# TKeyboard2_2021-07-30.net
KiCad netlist of a schematic drawn in Altium Designer
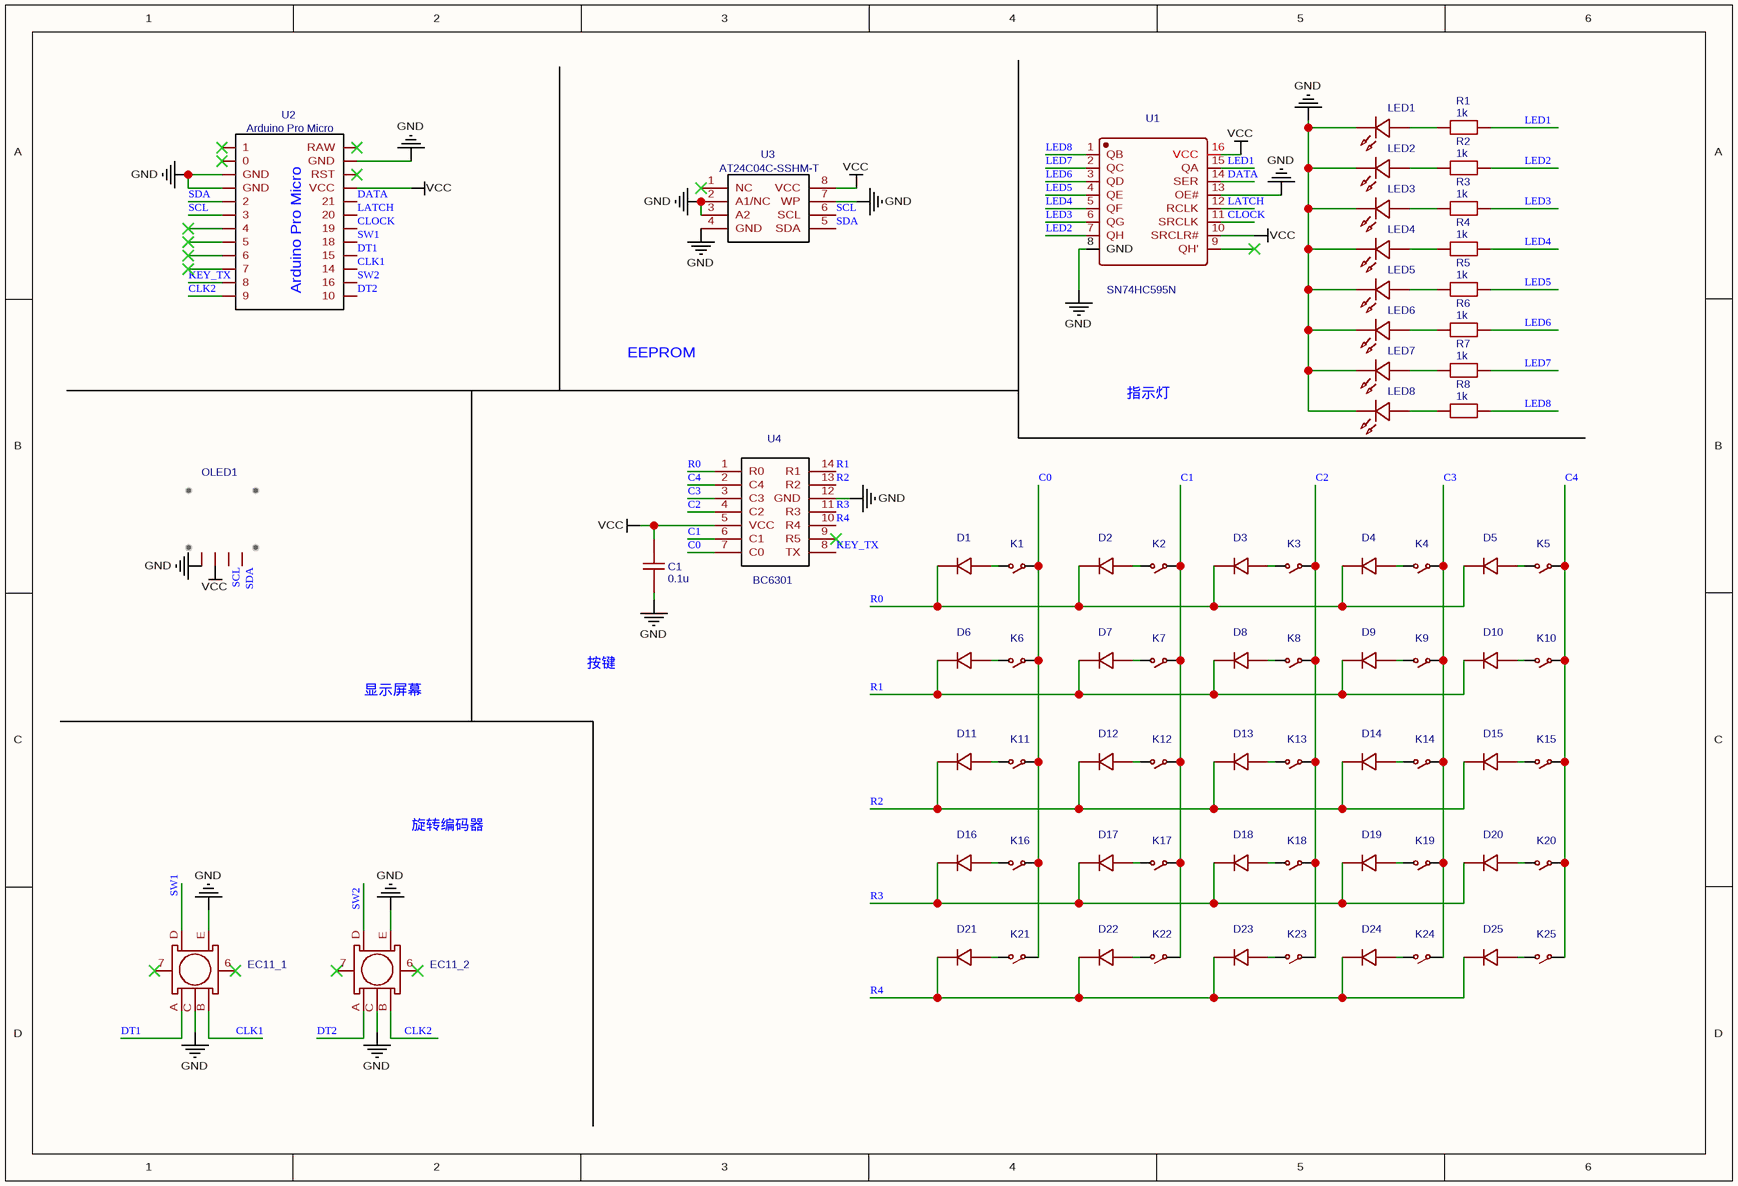
[diagram p0: TKeyboard2_2021-07-30.schdoc]

(export (version "E")
  (design (tool "Eeschema 10.0.6"))
  (components
    (comp (ref "C1")
      (value "0.1u")
      (fields (field (name "CONTRIBUTOR") "LCEDA_Lib"))
      (libsource (lib "altium-import") (part "root_1_0.1u_"))
    )
    (comp (ref "D1")
      (value "1N4148WS")
      (fields (field (name "BOM_SUPPLIER PART") "C179718") (field (name "CONTRIBUTOR") "LCSC"))
      (libsource (lib "altium-import") (part "root_0_1N4148WS_"))
    )
    (comp (ref "D2")
      (value "1N4148WS")
      (fields (field (name "BOM_SUPPLIER PART") "C179718") (field (name "CONTRIBUTOR") "LCSC"))
      (libsource (lib "altium-import") (part "root_0_1N4148WS_"))
    )
    (comp (ref "D3")
      (value "1N4148WS")
      (fields (field (name "BOM_SUPPLIER PART") "C179718") (field (name "CONTRIBUTOR") "LCSC"))
      (libsource (lib "altium-import") (part "root_0_1N4148WS_"))
    )
    (comp (ref "D4")
      (value "1N4148WS")
      (fields (field (name "BOM_SUPPLIER PART") "C179718") (field (name "CONTRIBUTOR") "LCSC"))
      (libsource (lib "altium-import") (part "root_0_1N4148WS_"))
    )
    (comp (ref "D5")
      (value "1N4148WS")
      (fields (field (name "BOM_SUPPLIER PART") "C179718") (field (name "CONTRIBUTOR") "LCSC"))
      (libsource (lib "altium-import") (part "root_0_1N4148WS_"))
    )
    (comp (ref "D6")
      (value "1N4148WS")
      (fields (field (name "BOM_SUPPLIER PART") "C179718") (field (name "CONTRIBUTOR") "LCSC"))
      (libsource (lib "altium-import") (part "root_0_1N4148WS_"))
    )
    (comp (ref "D7")
      (value "1N4148WS")
      (fields (field (name "BOM_SUPPLIER PART") "C179718") (field (name "CONTRIBUTOR") "LCSC"))
      (libsource (lib "altium-import") (part "root_0_1N4148WS_"))
    )
    (comp (ref "D8")
      (value "1N4148WS")
      (fields (field (name "BOM_SUPPLIER PART") "C179718") (field (name "CONTRIBUTOR") "LCSC"))
      (libsource (lib "altium-import") (part "root_0_1N4148WS_"))
    )
    (comp (ref "D9")
      (value "1N4148WS")
      (fields (field (name "BOM_SUPPLIER PART") "C179718") (field (name "CONTRIBUTOR") "LCSC"))
      (libsource (lib "altium-import") (part "root_0_1N4148WS_"))
    )
    (comp (ref "D10")
      (value "1N4148WS")
      (fields (field (name "BOM_SUPPLIER PART") "C179718") (field (name "CONTRIBUTOR") "LCSC"))
      (libsource (lib "altium-import") (part "root_0_1N4148WS_"))
    )
    (comp (ref "D11")
      (value "1N4148WS")
      (fields (field (name "BOM_SUPPLIER PART") "C179718") (field (name "CONTRIBUTOR") "LCSC"))
      (libsource (lib "altium-import") (part "root_0_1N4148WS_"))
    )
    (comp (ref "D12")
      (value "1N4148WS")
      (fields (field (name "BOM_SUPPLIER PART") "C179718") (field (name "CONTRIBUTOR") "LCSC"))
      (libsource (lib "altium-import") (part "root_0_1N4148WS_"))
    )
    (comp (ref "D13")
      (value "1N4148WS")
      (fields (field (name "BOM_SUPPLIER PART") "C179718") (field (name "CONTRIBUTOR") "LCSC"))
      (libsource (lib "altium-import") (part "root_0_1N4148WS_"))
    )
    (comp (ref "D14")
      (value "1N4148WS")
      (fields (field (name "BOM_SUPPLIER PART") "C179718") (field (name "CONTRIBUTOR") "LCSC"))
      (libsource (lib "altium-import") (part "root_0_1N4148WS_"))
    )
    (comp (ref "D15")
      (value "1N4148WS")
      (fields (field (name "BOM_SUPPLIER PART") "C179718") (field (name "CONTRIBUTOR") "LCSC"))
      (libsource (lib "altium-import") (part "root_0_1N4148WS_"))
    )
    (comp (ref "D16")
      (value "1N4148WS")
      (fields (field (name "BOM_SUPPLIER PART") "C179718") (field (name "CONTRIBUTOR") "LCSC"))
      (libsource (lib "altium-import") (part "root_0_1N4148WS_"))
    )
    (comp (ref "D17")
      (value "1N4148WS")
      (fields (field (name "BOM_SUPPLIER PART") "C179718") (field (name "CONTRIBUTOR") "LCSC"))
      (libsource (lib "altium-import") (part "root_0_1N4148WS_"))
    )
    (comp (ref "D18")
      (value "1N4148WS")
      (fields (field (name "BOM_SUPPLIER PART") "C179718") (field (name "CONTRIBUTOR") "LCSC"))
      (libsource (lib "altium-import") (part "root_0_1N4148WS_"))
    )
    (comp (ref "D19")
      (value "1N4148WS")
      (fields (field (name "BOM_SUPPLIER PART") "C179718") (field (name "CONTRIBUTOR") "LCSC"))
      (libsource (lib "altium-import") (part "root_0_1N4148WS_"))
    )
    (comp (ref "D20")
      (value "1N4148WS")
      (fields (field (name "BOM_SUPPLIER PART") "C179718") (field (name "CONTRIBUTOR") "LCSC"))
      (libsource (lib "altium-import") (part "root_0_1N4148WS_"))
    )
    (comp (ref "D21")
      (value "1N4148WS")
      (fields (field (name "BOM_SUPPLIER PART") "C179718") (field (name "CONTRIBUTOR") "LCSC"))
      (libsource (lib "altium-import") (part "root_0_1N4148WS_"))
    )
    (comp (ref "D22")
      (value "1N4148WS")
      (fields (field (name "BOM_SUPPLIER PART") "C179718") (field (name "CONTRIBUTOR") "LCSC"))
      (libsource (lib "altium-import") (part "root_0_1N4148WS_"))
    )
    (comp (ref "D23")
      (value "1N4148WS")
      (fields (field (name "BOM_SUPPLIER PART") "C179718") (field (name "CONTRIBUTOR") "LCSC"))
      (libsource (lib "altium-import") (part "root_0_1N4148WS_"))
    )
    (comp (ref "D24")
      (value "1N4148WS")
      (fields (field (name "BOM_SUPPLIER PART") "C179718") (field (name "CONTRIBUTOR") "LCSC"))
      (libsource (lib "altium-import") (part "root_0_1N4148WS_"))
    )
    (comp (ref "D25")
      (value "1N4148WS")
      (fields (field (name "BOM_SUPPLIER PART") "C179718") (field (name "CONTRIBUTOR") "LCSC"))
      (libsource (lib "altium-import") (part "root_0_1N4148WS_"))
    )
    (comp (ref "EC11_1")
      (value "EC11E152T409")
      (fields (field (name "BOM_SUPPLIER PART") "C110314") (field (name "CONTRIBUTOR") "LCSC"))
      (libsource (lib "altium-import") (part "root_0_EC11E152T409_"))
    )
    (comp (ref "EC11_2")
      (value "EC11E152T409")
      (fields (field (name "BOM_SUPPLIER PART") "C110314") (field (name "CONTRIBUTOR") "LCSC"))
      (libsource (lib "altium-import") (part "root_0_EC11E152T409_"))
    )
    (comp (ref "K1")
      (value "CHERRY")
      (fields (field (name "CONTRIBUTOR") "nicholasyoo"))
      (libsource (lib "altium-import") (part "root_0_CHERRY_"))
    )
    (comp (ref "K2")
      (value "CHERRY")
      (fields (field (name "CONTRIBUTOR") "nicholasyoo"))
      (libsource (lib "altium-import") (part "root_0_CHERRY_"))
    )
    (comp (ref "K3")
      (value "CHERRY")
      (fields (field (name "CONTRIBUTOR") "nicholasyoo"))
      (libsource (lib "altium-import") (part "root_0_CHERRY_"))
    )
    (comp (ref "K4")
      (value "CHERRY")
      (fields (field (name "CONTRIBUTOR") "nicholasyoo"))
      (libsource (lib "altium-import") (part "root_0_CHERRY_"))
    )
    (comp (ref "K5")
      (value "CHERRY")
      (fields (field (name "CONTRIBUTOR") "nicholasyoo"))
      (libsource (lib "altium-import") (part "root_0_CHERRY_"))
    )
    (comp (ref "K6")
      (value "CHERRY")
      (fields (field (name "CONTRIBUTOR") "nicholasyoo"))
      (libsource (lib "altium-import") (part "root_0_CHERRY_"))
    )
    (comp (ref "K7")
      (value "CHERRY")
      (fields (field (name "CONTRIBUTOR") "nicholasyoo"))
      (libsource (lib "altium-import") (part "root_0_CHERRY_"))
    )
    (comp (ref "K8")
      (value "CHERRY")
      (fields (field (name "CONTRIBUTOR") "nicholasyoo"))
      (libsource (lib "altium-import") (part "root_0_CHERRY_"))
    )
    (comp (ref "K9")
      (value "CHERRY")
      (fields (field (name "CONTRIBUTOR") "nicholasyoo"))
      (libsource (lib "altium-import") (part "root_0_CHERRY_"))
    )
    (comp (ref "K10")
      (value "CHERRY")
      (fields (field (name "CONTRIBUTOR") "nicholasyoo"))
      (libsource (lib "altium-import") (part "root_0_CHERRY_"))
    )
    (comp (ref "K11")
      (value "CHERRY")
      (fields (field (name "CONTRIBUTOR") "nicholasyoo"))
      (libsource (lib "altium-import") (part "root_0_CHERRY_"))
    )
    (comp (ref "K12")
      (value "CHERRY")
      (fields (field (name "CONTRIBUTOR") "nicholasyoo"))
      (libsource (lib "altium-import") (part "root_0_CHERRY_"))
    )
    (comp (ref "K13")
      (value "CHERRY")
      (fields (field (name "CONTRIBUTOR") "nicholasyoo"))
      (libsource (lib "altium-import") (part "root_0_CHERRY_"))
    )
    (comp (ref "K14")
      (value "CHERRY")
      (fields (field (name "CONTRIBUTOR") "nicholasyoo"))
      (libsource (lib "altium-import") (part "root_0_CHERRY_"))
    )
    (comp (ref "K15")
      (value "CHERRY")
      (fields (field (name "CONTRIBUTOR") "nicholasyoo"))
      (libsource (lib "altium-import") (part "root_0_CHERRY_"))
    )
    (comp (ref "K16")
      (value "CHERRY")
      (fields (field (name "CONTRIBUTOR") "nicholasyoo"))
      (libsource (lib "altium-import") (part "root_0_CHERRY_"))
    )
    (comp (ref "K17")
      (value "CHERRY")
      (fields (field (name "CONTRIBUTOR") "nicholasyoo"))
      (libsource (lib "altium-import") (part "root_0_CHERRY_"))
    )
    (comp (ref "K18")
      (value "CHERRY")
      (fields (field (name "CONTRIBUTOR") "nicholasyoo"))
      (libsource (lib "altium-import") (part "root_0_CHERRY_"))
    )
    (comp (ref "K19")
      (value "CHERRY")
      (fields (field (name "CONTRIBUTOR") "nicholasyoo"))
      (libsource (lib "altium-import") (part "root_0_CHERRY_"))
    )
    (comp (ref "K20")
      (value "CHERRY")
      (fields (field (name "CONTRIBUTOR") "nicholasyoo"))
      (libsource (lib "altium-import") (part "root_0_CHERRY_"))
    )
    (comp (ref "K21")
      (value "CHERRY")
      (fields (field (name "CONTRIBUTOR") "nicholasyoo"))
      (libsource (lib "") (part "root_0_CHERRY__1"))
    )
    (comp (ref "K22")
      (value "CHERRY")
      (fields (field (name "CONTRIBUTOR") "nicholasyoo"))
      (libsource (lib "") (part "root_0_CHERRY__1"))
    )
    (comp (ref "K23")
      (value "CHERRY")
      (fields (field (name "CONTRIBUTOR") "nicholasyoo"))
      (libsource (lib "") (part "root_0_CHERRY__1"))
    )
    (comp (ref "K24")
      (value "CHERRY")
      (fields (field (name "CONTRIBUTOR") "nicholasyoo"))
      (libsource (lib "") (part "root_0_CHERRY__1"))
    )
    (comp (ref "K25")
      (value "CHERRY")
      (fields (field (name "CONTRIBUTOR") "nicholasyoo"))
      (libsource (lib "") (part "root_0_CHERRY__1"))
    )
    (comp (ref "LED1")
      (value "LED-0805_R")
      (fields
        (field (name "BOM_MANUFACTURER PART") "17-21SURC/S530-A3/TR8")
        (field (name "BOM_SUPPLIER PART") "C72037")
        (field (name "CONTRIBUTOR") "LCEDA_Lib")
      )
      (libsource (lib "altium-import") (part "root_2_LED-0805_R_"))
    )
    (comp (ref "LED2")
      (value "LED-0805_R")
      (fields
        (field (name "BOM_MANUFACTURER PART") "17-21SURC/S530-A3/TR8")
        (field (name "BOM_SUPPLIER PART") "C72037")
        (field (name "CONTRIBUTOR") "LCEDA_Lib")
      )
      (libsource (lib "altium-import") (part "root_2_LED-0805_R_"))
    )
    (comp (ref "LED3")
      (value "LED-0805_R")
      (fields
        (field (name "BOM_MANUFACTURER PART") "17-21SURC/S530-A3/TR8")
        (field (name "BOM_SUPPLIER PART") "C72037")
        (field (name "CONTRIBUTOR") "LCEDA_Lib")
      )
      (libsource (lib "altium-import") (part "root_2_LED-0805_R_"))
    )
    (comp (ref "LED4")
      (value "LED-0805_R")
      (fields
        (field (name "BOM_MANUFACTURER PART") "17-21SURC/S530-A3/TR8")
        (field (name "BOM_SUPPLIER PART") "C72037")
        (field (name "CONTRIBUTOR") "LCEDA_Lib")
      )
      (libsource (lib "altium-import") (part "root_2_LED-0805_R_"))
    )
    (comp (ref "LED5")
      (value "LED-0805_R")
      (fields
        (field (name "BOM_MANUFACTURER PART") "17-21SURC/S530-A3/TR8")
        (field (name "BOM_SUPPLIER PART") "C72037")
        (field (name "CONTRIBUTOR") "LCEDA_Lib")
      )
      (libsource (lib "altium-import") (part "root_2_LED-0805_R_"))
    )
    (comp (ref "LED6")
      (value "LED-0805_R")
      (fields
        (field (name "BOM_MANUFACTURER PART") "17-21SURC/S530-A3/TR8")
        (field (name "BOM_SUPPLIER PART") "C72037")
        (field (name "CONTRIBUTOR") "LCEDA_Lib")
      )
      (libsource (lib "altium-import") (part "root_2_LED-0805_R_"))
    )
    (comp (ref "LED7")
      (value "LED-0805_R")
      (fields
        (field (name "BOM_MANUFACTURER PART") "17-21SURC/S530-A3/TR8")
        (field (name "BOM_SUPPLIER PART") "C72037")
        (field (name "CONTRIBUTOR") "LCEDA_Lib")
      )
      (libsource (lib "altium-import") (part "root_2_LED-0805_R_"))
    )
    (comp (ref "LED8")
      (value "LED-0805_R")
      (fields
        (field (name "BOM_MANUFACTURER PART") "17-21SURC/S530-A3/TR8")
        (field (name "BOM_SUPPLIER PART") "C72037")
        (field (name "CONTRIBUTOR") "LCEDA_Lib")
      )
      (libsource (lib "altium-import") (part "root_2_LED-0805_R_"))
    )
    (comp (ref "OLED1")
      (value "0.96OLED_4P")
      (fields (field (name "CONTRIBUTOR") "LCEDA_Lib"))
      (libsource (lib "altium-import") (part "root_0_0.96OLED_4P_"))
    )
    (comp (ref "R1")
      (value "1k")
      (fields (field (name "CONTRIBUTOR") "LCEDA_Lib"))
      (libsource (lib "altium-import") (part "root_2_1k_"))
    )
    (comp (ref "R2")
      (value "1k")
      (fields (field (name "CONTRIBUTOR") "LCEDA_Lib"))
      (libsource (lib "altium-import") (part "root_2_1k_"))
    )
    (comp (ref "R3")
      (value "1k")
      (fields (field (name "CONTRIBUTOR") "LCEDA_Lib"))
      (libsource (lib "altium-import") (part "root_2_1k_"))
    )
    (comp (ref "R4")
      (value "1k")
      (fields (field (name "CONTRIBUTOR") "LCEDA_Lib"))
      (libsource (lib "altium-import") (part "root_2_1k_"))
    )
    (comp (ref "R5")
      (value "1k")
      (fields (field (name "CONTRIBUTOR") "LCEDA_Lib"))
      (libsource (lib "altium-import") (part "root_2_1k_"))
    )
    (comp (ref "R6")
      (value "1k")
      (fields (field (name "CONTRIBUTOR") "LCEDA_Lib"))
      (libsource (lib "altium-import") (part "root_2_1k_"))
    )
    (comp (ref "R7")
      (value "1k")
      (fields (field (name "CONTRIBUTOR") "LCEDA_Lib"))
      (libsource (lib "altium-import") (part "root_2_1k_"))
    )
    (comp (ref "R8")
      (value "1k")
      (fields (field (name "CONTRIBUTOR") "LCEDA_Lib"))
      (libsource (lib "altium-import") (part "root_2_1k_"))
    )
    (comp (ref "U1")
      (value "SN74HC595N")
      (fields (field (name "BOM_SUPPLIER PART") "C78711"))
      (libsource (lib "altium-import") (part "root_0_SN74HC595N_"))
    )
    (comp (ref "U2")
      (value "Arduino Pro Micro")
      (fields (field (name "CONTRIBUTOR") "ruxia"))
      (libsource (lib "altium-import") (part "root_0_Arduino Pro Micro_"))
    )
    (comp (ref "U3")
      (value "AT24C04C-SSHM-T")
      (fields (field (name "BOM_SUPPLIER PART") "C6205"))
      (libsource (lib "altium-import") (part "root_0_AT24C04C-SSHM-T_"))
    )
    (comp (ref "U4")
      (value "BC6301")
      (fields (field (name "CONTRIBUTOR") "pc8051"))
      (libsource (lib "altium-import") (part "root_0_BC6301_"))
    )
  )
  (nets
    (net (code "1") (name "/C0") (class "Default")
      (node (ref "K1") (pin "1") (pinfunction "1_1") (pintype "passive"))
      (node (ref "K11") (pin "1") (pinfunction "1_1") (pintype "passive"))
      (node (ref "K16") (pin "1") (pinfunction "1_1") (pintype "passive"))
      (node (ref "K21") (pin "1") (pinfunction "1_1") (pintype "passive"))
      (node (ref "K6") (pin "1") (pinfunction "1_1") (pintype "passive"))
      (node (ref "U4") (pin "7") (pinfunction "C0_7") (pintype "passive"))
    )
    (net (code "2") (name "/C1") (class "Default")
      (node (ref "K12") (pin "1") (pinfunction "1_1") (pintype "passive"))
      (node (ref "K17") (pin "1") (pinfunction "1_1") (pintype "passive"))
      (node (ref "K2") (pin "1") (pinfunction "1_1") (pintype "passive"))
      (node (ref "K22") (pin "1") (pinfunction "1_1") (pintype "passive"))
      (node (ref "K7") (pin "1") (pinfunction "1_1") (pintype "passive"))
      (node (ref "U4") (pin "6") (pinfunction "C1_6") (pintype "passive"))
    )
    (net (code "3") (name "/C2") (class "Default")
      (node (ref "K13") (pin "1") (pinfunction "1_1") (pintype "passive"))
      (node (ref "K18") (pin "1") (pinfunction "1_1") (pintype "passive"))
      (node (ref "K23") (pin "1") (pinfunction "1_1") (pintype "passive"))
      (node (ref "K3") (pin "1") (pinfunction "1_1") (pintype "passive"))
      (node (ref "K8") (pin "1") (pinfunction "1_1") (pintype "passive"))
      (node (ref "U4") (pin "4") (pinfunction "C2_4") (pintype "passive"))
    )
    (net (code "4") (name "/C3") (class "Default")
      (node (ref "K14") (pin "1") (pinfunction "1_1") (pintype "passive"))
      (node (ref "K19") (pin "1") (pinfunction "1_1") (pintype "passive"))
      (node (ref "K24") (pin "1") (pinfunction "1_1") (pintype "passive"))
      (node (ref "K4") (pin "1") (pinfunction "1_1") (pintype "passive"))
      (node (ref "K9") (pin "1") (pinfunction "1_1") (pintype "passive"))
      (node (ref "U4") (pin "3") (pinfunction "C3_3") (pintype "passive"))
    )
    (net (code "5") (name "/C4") (class "Default")
      (node (ref "K10") (pin "1") (pinfunction "1_1") (pintype "passive"))
      (node (ref "K15") (pin "1") (pinfunction "1_1") (pintype "passive"))
      (node (ref "K20") (pin "1") (pinfunction "1_1") (pintype "passive"))
      (node (ref "K25") (pin "1") (pinfunction "1_1") (pintype "passive"))
      (node (ref "K5") (pin "1") (pinfunction "1_1") (pintype "passive"))
      (node (ref "U4") (pin "2") (pinfunction "C4_2") (pintype "passive"))
    )
    (net (code "6") (name "/CLK1") (class "Default")
      (node (ref "EC11_1") (pin "B") (pinfunction "B_B") (pintype "passive"))
      (node (ref "U2") (pin "15") (pinfunction "14_15") (pintype "passive"))
    )
    (net (code "7") (name "/CLK2") (class "Default")
      (node (ref "EC11_2") (pin "B") (pinfunction "B_B") (pintype "passive"))
      (node (ref "U2") (pin "12") (pinfunction "9_12") (pintype "passive"))
    )
    (net (code "8") (name "/CLOCK") (class "Default")
      (node (ref "U1") (pin "11") (pinfunction "SRCLK_11") (pintype "passive"))
      (node (ref "U2") (pin "18") (pinfunction "19_18") (pintype "passive"))
    )
    (net (code "9") (name "/DATA") (class "Default")
      (node (ref "U1") (pin "14") (pinfunction "SER_14") (pintype "passive"))
      (node (ref "U2") (pin "20") (pinfunction "21_20") (pintype "passive"))
    )
    (net (code "10") (name "/DT1") (class "Default")
      (node (ref "EC11_1") (pin "A") (pinfunction "A_A") (pintype "passive"))
      (node (ref "U2") (pin "16") (pinfunction "15_16") (pintype "passive"))
    )
    (net (code "11") (name "/DT2") (class "Default")
      (node (ref "EC11_2") (pin "A") (pinfunction "A_A") (pintype "passive"))
      (node (ref "U2") (pin "13") (pinfunction "10_13") (pintype "passive"))
    )
    (net (code "12") (name "/KEY_TX") (class "Default")
      (node (ref "U2") (pin "11") (pinfunction "8_11") (pintype "passive"))
      (node (ref "U4") (pin "8") (pinfunction "TX_8") (pintype "passive"))
    )
    (net (code "13") (name "/LATCH") (class "Default")
      (node (ref "U1") (pin "12") (pinfunction "RCLK_12") (pintype "passive"))
      (node (ref "U2") (pin "19") (pinfunction "20_19") (pintype "passive"))
    )
    (net (code "14") (name "/LED1") (class "Default")
      (node (ref "R1") (pin "1") (pinfunction "1_1") (pintype "passive"))
      (node (ref "U1") (pin "15") (pinfunction "QA_15") (pintype "passive"))
    )
    (net (code "15") (name "/LED2") (class "Default")
      (node (ref "R2") (pin "1") (pinfunction "1_1") (pintype "passive"))
      (node (ref "U1") (pin "7") (pinfunction "QH_7") (pintype "passive"))
    )
    (net (code "16") (name "/LED3") (class "Default")
      (node (ref "R3") (pin "1") (pinfunction "1_1") (pintype "passive"))
      (node (ref "U1") (pin "6") (pinfunction "QG_6") (pintype "passive"))
    )
    (net (code "17") (name "/LED4") (class "Default")
      (node (ref "R4") (pin "1") (pinfunction "1_1") (pintype "passive"))
      (node (ref "U1") (pin "5") (pinfunction "QF_5") (pintype "passive"))
    )
    (net (code "18") (name "/LED5") (class "Default")
      (node (ref "R5") (pin "1") (pinfunction "1_1") (pintype "passive"))
      (node (ref "U1") (pin "4") (pinfunction "QE_4") (pintype "passive"))
    )
    (net (code "19") (name "/LED6") (class "Default")
      (node (ref "R6") (pin "1") (pinfunction "1_1") (pintype "passive"))
      (node (ref "U1") (pin "3") (pinfunction "QD_3") (pintype "passive"))
    )
    (net (code "20") (name "/LED7") (class "Default")
      (node (ref "R7") (pin "1") (pinfunction "1_1") (pintype "passive"))
      (node (ref "U1") (pin "2") (pinfunction "QC_2") (pintype "passive"))
    )
    (net (code "21") (name "/LED8") (class "Default")
      (node (ref "R8") (pin "1") (pinfunction "1_1") (pintype "passive"))
      (node (ref "U1") (pin "1") (pinfunction "QB_1") (pintype "passive"))
    )
    (net (code "22") (name "/R0") (class "Default")
      (node (ref "D1") (pin "1") (pinfunction "K_1") (pintype "passive"))
      (node (ref "D2") (pin "1") (pinfunction "K_1") (pintype "passive"))
      (node (ref "D3") (pin "1") (pinfunction "K_1") (pintype "passive"))
      (node (ref "D4") (pin "1") (pinfunction "K_1") (pintype "passive"))
      (node (ref "D5") (pin "1") (pinfunction "K_1") (pintype "passive"))
      (node (ref "U4") (pin "1") (pinfunction "R0_1") (pintype "passive"))
    )
    (net (code "23") (name "/R1") (class "Default")
      (node (ref "D10") (pin "1") (pinfunction "K_1") (pintype "passive"))
      (node (ref "D6") (pin "1") (pinfunction "K_1") (pintype "passive"))
      (node (ref "D7") (pin "1") (pinfunction "K_1") (pintype "passive"))
      (node (ref "D8") (pin "1") (pinfunction "K_1") (pintype "passive"))
      (node (ref "D9") (pin "1") (pinfunction "K_1") (pintype "passive"))
      (node (ref "U4") (pin "14") (pinfunction "R1_14") (pintype "passive"))
    )
    (net (code "24") (name "/R2") (class "Default")
      (node (ref "D11") (pin "1") (pinfunction "K_1") (pintype "passive"))
      (node (ref "D12") (pin "1") (pinfunction "K_1") (pintype "passive"))
      (node (ref "D13") (pin "1") (pinfunction "K_1") (pintype "passive"))
      (node (ref "D14") (pin "1") (pinfunction "K_1") (pintype "passive"))
      (node (ref "D15") (pin "1") (pinfunction "K_1") (pintype "passive"))
      (node (ref "U4") (pin "13") (pinfunction "R2_13") (pintype "passive"))
    )
    (net (code "25") (name "/R3") (class "Default")
      (node (ref "D16") (pin "1") (pinfunction "K_1") (pintype "passive"))
      (node (ref "D17") (pin "1") (pinfunction "K_1") (pintype "passive"))
      (node (ref "D18") (pin "1") (pinfunction "K_1") (pintype "passive"))
      (node (ref "D19") (pin "1") (pinfunction "K_1") (pintype "passive"))
      (node (ref "D20") (pin "1") (pinfunction "K_1") (pintype "passive"))
      (node (ref "U4") (pin "11") (pinfunction "R3_11") (pintype "passive"))
    )
    (net (code "26") (name "/R4") (class "Default")
      (node (ref "D21") (pin "1") (pinfunction "K_1") (pintype "passive"))
      (node (ref "D22") (pin "1") (pinfunction "K_1") (pintype "passive"))
      (node (ref "D23") (pin "1") (pinfunction "K_1") (pintype "passive"))
      (node (ref "D24") (pin "1") (pinfunction "K_1") (pintype "passive"))
      (node (ref "D25") (pin "1") (pinfunction "K_1") (pintype "passive"))
      (node (ref "U4") (pin "10") (pinfunction "R4_10") (pintype "passive"))
    )
    (net (code "27") (name "/SCL") (class "Default")
      (node (ref "OLED1") (pin "3") (pinfunction "3_3") (pintype "passive"))
      (node (ref "U2") (pin "6") (pinfunction "3_6") (pintype "passive"))
      (node (ref "U3") (pin "6") (pinfunction "SCL_6") (pintype "passive"))
    )
    (net (code "28") (name "/SDA") (class "Default")
      (node (ref "OLED1") (pin "4") (pinfunction "4_4") (pintype "passive"))
      (node (ref "U2") (pin "5") (pinfunction "2_5") (pintype "passive"))
      (node (ref "U3") (pin "5") (pinfunction "SDA_5") (pintype "passive"))
    )
    (net (code "29") (name "/SW1") (class "Default")
      (node (ref "EC11_1") (pin "D") (pinfunction "D_D") (pintype "passive"))
      (node (ref "U2") (pin "17") (pinfunction "18_17") (pintype "passive"))
    )
    (net (code "30") (name "/SW2") (class "Default")
      (node (ref "EC11_2") (pin "D") (pinfunction "D_D") (pintype "passive"))
      (node (ref "U2") (pin "14") (pinfunction "16_14") (pintype "passive"))
    )
    (net (code "31") (name "GND") (class "Default")
      (node (ref "C1") (pin "1") (pinfunction "1_1") (pintype "passive"))
      (node (ref "EC11_1") (pin "C") (pinfunction "C_C") (pintype "passive"))
      (node (ref "EC11_1") (pin "E") (pinfunction "E_E") (pintype "passive"))
      (node (ref "EC11_2") (pin "C") (pinfunction "C_C") (pintype "passive"))
      (node (ref "EC11_2") (pin "E") (pinfunction "E_E") (pintype "passive"))
      (node (ref "LED1") (pin "2") (pinfunction "2_2") (pintype "passive"))
      (node (ref "LED2") (pin "2") (pinfunction "2_2") (pintype "passive"))
      (node (ref "LED3") (pin "2") (pinfunction "2_2") (pintype "passive"))
      (node (ref "LED4") (pin "2") (pinfunction "2_2") (pintype "passive"))
      (node (ref "LED5") (pin "2") (pinfunction "2_2") (pintype "passive"))
      (node (ref "LED6") (pin "2") (pinfunction "2_2") (pintype "passive"))
      (node (ref "LED7") (pin "2") (pinfunction "2_2") (pintype "passive"))
      (node (ref "LED8") (pin "2") (pinfunction "2_2") (pintype "passive"))
      (node (ref "OLED1") (pin "1") (pinfunction "1_1") (pintype "passive"))
      (node (ref "U1") (pin "13") (pinfunction "OE#_13") (pintype "passive"))
      (node (ref "U1") (pin "8") (pinfunction "GND_8") (pintype "passive"))
      (node (ref "U2") (pin "23") (pinfunction "GND_23") (pintype "passive"))
      (node (ref "U2") (pin "3") (pinfunction "GND_3") (pintype "passive"))
      (node (ref "U2") (pin "4") (pinfunction "GND_4") (pintype "passive"))
      (node (ref "U3") (pin "2") (pinfunction "A1/NC_2") (pintype "passive"))
      (node (ref "U3") (pin "3") (pinfunction "A2_3") (pintype "passive"))
      (node (ref "U3") (pin "4") (pinfunction "GND_4") (pintype "passive"))
      (node (ref "U3") (pin "7") (pinfunction "WP_7") (pintype "passive"))
      (node (ref "U4") (pin "12") (pinfunction "GND_12") (pintype "passive"))
    )
    (net (code "32") (name "Net-(D1-A)") (class "Default")
      (node (ref "D1") (pin "2") (pinfunction "A_2") (pintype "passive"))
      (node (ref "K1") (pin "2") (pinfunction "2_2") (pintype "passive"))
    )
    (net (code "33") (name "Net-(D2-A)") (class "Default")
      (node (ref "D2") (pin "2") (pinfunction "A_2") (pintype "passive"))
      (node (ref "K2") (pin "2") (pinfunction "2_2") (pintype "passive"))
    )
    (net (code "34") (name "Net-(D3-A)") (class "Default")
      (node (ref "D3") (pin "2") (pinfunction "A_2") (pintype "passive"))
      (node (ref "K3") (pin "2") (pinfunction "2_2") (pintype "passive"))
    )
    (net (code "35") (name "Net-(D4-A)") (class "Default")
      (node (ref "D4") (pin "2") (pinfunction "A_2") (pintype "passive"))
      (node (ref "K4") (pin "2") (pinfunction "2_2") (pintype "passive"))
    )
    (net (code "36") (name "Net-(D5-A)") (class "Default")
      (node (ref "D5") (pin "2") (pinfunction "A_2") (pintype "passive"))
      (node (ref "K5") (pin "2") (pinfunction "2_2") (pintype "passive"))
    )
    (net (code "37") (name "Net-(D6-A)") (class "Default")
      (node (ref "D6") (pin "2") (pinfunction "A_2") (pintype "passive"))
      (node (ref "K6") (pin "2") (pinfunction "2_2") (pintype "passive"))
    )
    (net (code "38") (name "Net-(D7-A)") (class "Default")
      (node (ref "D7") (pin "2") (pinfunction "A_2") (pintype "passive"))
      (node (ref "K7") (pin "2") (pinfunction "2_2") (pintype "passive"))
    )
    (net (code "39") (name "Net-(D8-A)") (class "Default")
      (node (ref "D8") (pin "2") (pinfunction "A_2") (pintype "passive"))
      (node (ref "K8") (pin "2") (pinfunction "2_2") (pintype "passive"))
    )
    (net (code "40") (name "Net-(D9-A)") (class "Default")
      (node (ref "D9") (pin "2") (pinfunction "A_2") (pintype "passive"))
      (node (ref "K9") (pin "2") (pinfunction "2_2") (pintype "passive"))
    )
    (net (code "41") (name "Net-(D10-A)") (class "Default")
      (node (ref "D10") (pin "2") (pinfunction "A_2") (pintype "passive"))
      (node (ref "K10") (pin "2") (pinfunction "2_2") (pintype "passive"))
    )
    (net (code "42") (name "Net-(D11-A)") (class "Default")
      (node (ref "D11") (pin "2") (pinfunction "A_2") (pintype "passive"))
      (node (ref "K11") (pin "2") (pinfunction "2_2") (pintype "passive"))
    )
    (net (code "43") (name "Net-(D12-A)") (class "Default")
      (node (ref "D12") (pin "2") (pinfunction "A_2") (pintype "passive"))
      (node (ref "K12") (pin "2") (pinfunction "2_2") (pintype "passive"))
    )
    (net (code "44") (name "Net-(D13-A)") (class "Default")
      (node (ref "D13") (pin "2") (pinfunction "A_2") (pintype "passive"))
      (node (ref "K13") (pin "2") (pinfunction "2_2") (pintype "passive"))
    )
    (net (code "45") (name "Net-(D14-A)") (class "Default")
      (node (ref "D14") (pin "2") (pinfunction "A_2") (pintype "passive"))
      (node (ref "K14") (pin "2") (pinfunction "2_2") (pintype "passive"))
    )
    (net (code "46") (name "Net-(D15-A)") (class "Default")
      (node (ref "D15") (pin "2") (pinfunction "A_2") (pintype "passive"))
      (node (ref "K15") (pin "2") (pinfunction "2_2") (pintype "passive"))
    )
    (net (code "47") (name "Net-(D16-A)") (class "Default")
      (node (ref "D16") (pin "2") (pinfunction "A_2") (pintype "passive"))
      (node (ref "K16") (pin "2") (pinfunction "2_2") (pintype "passive"))
    )
    (net (code "48") (name "Net-(D17-A)") (class "Default")
      (node (ref "D17") (pin "2") (pinfunction "A_2") (pintype "passive"))
      (node (ref "K17") (pin "2") (pinfunction "2_2") (pintype "passive"))
    )
    (net (code "49") (name "Net-(D18-A)") (class "Default")
      (node (ref "D18") (pin "2") (pinfunction "A_2") (pintype "passive"))
      (node (ref "K18") (pin "2") (pinfunction "2_2") (pintype "passive"))
    )
    (net (code "50") (name "Net-(D19-A)") (class "Default")
      (node (ref "D19") (pin "2") (pinfunction "A_2") (pintype "passive"))
      (node (ref "K19") (pin "2") (pinfunction "2_2") (pintype "passive"))
    )
    (net (code "51") (name "Net-(D20-A)") (class "Default")
      (node (ref "D20") (pin "2") (pinfunction "A_2") (pintype "passive"))
      (node (ref "K20") (pin "2") (pinfunction "2_2") (pintype "passive"))
    )
    (net (code "52") (name "Net-(D21-A)") (class "Default")
      (node (ref "D21") (pin "2") (pinfunction "A_2") (pintype "passive"))
      (node (ref "K21") (pin "2") (pinfunction "2_2") (pintype "passive"))
    )
    (net (code "53") (name "Net-(D22-A)") (class "Default")
      (node (ref "D22") (pin "2") (pinfunction "A_2") (pintype "passive"))
      (node (ref "K22") (pin "2") (pinfunction "2_2") (pintype "passive"))
    )
    (net (code "54") (name "Net-(D23-A)") (class "Default")
      (node (ref "D23") (pin "2") (pinfunction "A_2") (pintype "passive"))
      (node (ref "K23") (pin "2") (pinfunction "2_2") (pintype "passive"))
    )
    (net (code "55") (name "Net-(D24-A)") (class "Default")
      (node (ref "D24") (pin "2") (pinfunction "A_2") (pintype "passive"))
      (node (ref "K24") (pin "2") (pinfunction "2_2") (pintype "passive"))
    )
    (net (code "56") (name "Net-(D25-A)") (class "Default")
      (node (ref "D25") (pin "2") (pinfunction "A_2") (pintype "passive"))
      (node (ref "K25") (pin "2") (pinfunction "2_2") (pintype "passive"))
    )
    (net (code "57") (name "Net-(LED1-Pad1)") (class "Default")
      (node (ref "LED1") (pin "1") (pinfunction "1_1") (pintype "passive"))
      (node (ref "R1") (pin "2") (pinfunction "2_2") (pintype "passive"))
    )
    (net (code "58") (name "Net-(LED2-Pad1)") (class "Default")
      (node (ref "LED2") (pin "1") (pinfunction "1_1") (pintype "passive"))
      (node (ref "R2") (pin "2") (pinfunction "2_2") (pintype "passive"))
    )
    (net (code "59") (name "Net-(LED3-Pad1)") (class "Default")
      (node (ref "LED3") (pin "1") (pinfunction "1_1") (pintype "passive"))
      (node (ref "R3") (pin "2") (pinfunction "2_2") (pintype "passive"))
    )
    (net (code "60") (name "Net-(LED4-Pad1)") (class "Default")
      (node (ref "LED4") (pin "1") (pinfunction "1_1") (pintype "passive"))
      (node (ref "R4") (pin "2") (pinfunction "2_2") (pintype "passive"))
    )
    (net (code "61") (name "Net-(LED5-Pad1)") (class "Default")
      (node (ref "LED5") (pin "1") (pinfunction "1_1") (pintype "passive"))
      (node (ref "R5") (pin "2") (pinfunction "2_2") (pintype "passive"))
    )
    (net (code "62") (name "Net-(LED6-Pad1)") (class "Default")
      (node (ref "LED6") (pin "1") (pinfunction "1_1") (pintype "passive"))
      (node (ref "R6") (pin "2") (pinfunction "2_2") (pintype "passive"))
    )
    (net (code "63") (name "Net-(LED7-Pad1)") (class "Default")
      (node (ref "LED7") (pin "1") (pinfunction "1_1") (pintype "passive"))
      (node (ref "R7") (pin "2") (pinfunction "2_2") (pintype "passive"))
    )
    (net (code "64") (name "Net-(LED8-Pad1)") (class "Default")
      (node (ref "LED8") (pin "1") (pinfunction "1_1") (pintype "passive"))
      (node (ref "R8") (pin "2") (pinfunction "2_2") (pintype "passive"))
    )
    (net (code "65") (name "VCC") (class "Default")
      (node (ref "C1") (pin "2") (pinfunction "2_2") (pintype "passive"))
      (node (ref "OLED1") (pin "2") (pinfunction "2_2") (pintype "passive"))
      (node (ref "U1") (pin "10") (pinfunction "SRCLR#_10") (pintype "passive"))
      (node (ref "U1") (pin "16") (pinfunction "VCC_16") (pintype "passive"))
      (node (ref "U2") (pin "21") (pinfunction "VCC_21") (pintype "passive"))
      (node (ref "U3") (pin "8") (pinfunction "VCC_8") (pintype "passive"))
      (node (ref "U4") (pin "5") (pinfunction "VCC_5") (pintype "passive"))
    )
    (net (code "66") (name "unconnected-(EC11_1-Pad6)") (class "Default")
      (node (ref "EC11_1") (pin "6") (pinfunction "6_6") (pintype "passive+no_connect"))
    )
    (net (code "67") (name "unconnected-(EC11_1-Pad7)") (class "Default")
      (node (ref "EC11_1") (pin "7") (pinfunction "7_7") (pintype "passive+no_connect"))
    )
    (net (code "68") (name "unconnected-(EC11_2-Pad6)") (class "Default")
      (node (ref "EC11_2") (pin "6") (pinfunction "6_6") (pintype "passive+no_connect"))
    )
    (net (code "69") (name "unconnected-(EC11_2-Pad7)") (class "Default")
      (node (ref "EC11_2") (pin "7") (pinfunction "7_7") (pintype "passive+no_connect"))
    )
    (net (code "70") (name "unconnected-(U1-QH'-Pad9)") (class "Default")
      (node (ref "U1") (pin "9") (pinfunction "QH'_9") (pintype "passive+no_connect"))
    )
    (net (code "71") (name "unconnected-(U2-0-Pad2)") (class "Default")
      (node (ref "U2") (pin "2") (pinfunction "0_2") (pintype "passive+no_connect"))
    )
    (net (code "72") (name "unconnected-(U2-4-Pad7)") (class "Default")
      (node (ref "U2") (pin "7") (pinfunction "4_7") (pintype "passive+no_connect"))
    )
    (net (code "73") (name "unconnected-(U2-5-Pad8)") (class "Default")
      (node (ref "U2") (pin "8") (pinfunction "5_8") (pintype "passive+no_connect"))
    )
    (net (code "74") (name "unconnected-(U2-6-Pad9)") (class "Default")
      (node (ref "U2") (pin "9") (pinfunction "6_9") (pintype "passive+no_connect"))
    )
    (net (code "75") (name "unconnected-(U2-7-Pad10)") (class "Default")
      (node (ref "U2") (pin "10") (pinfunction "7_10") (pintype "passive+no_connect"))
    )
    (net (code "76") (name "unconnected-(U2-Pad1)") (class "Default")
      (node (ref "U2") (pin "1") (pinfunction "1_1") (pintype "passive+no_connect"))
    )
    (net (code "77") (name "unconnected-(U2-RAW-Pad24)") (class "Default")
      (node (ref "U2") (pin "24") (pinfunction "RAW_24") (pintype "passive+no_connect"))
    )
    (net (code "78") (name "unconnected-(U2-RST-Pad22)") (class "Default")
      (node (ref "U2") (pin "22") (pinfunction "RST_22") (pintype "passive+no_connect"))
    )
    (net (code "79") (name "unconnected-(U3-NC-Pad1)") (class "Default")
      (node (ref "U3") (pin "1") (pinfunction "NC_1") (pintype "passive+no_connect"))
    )
    (net (code "80") (name "unconnected-(U4-R5-Pad9)") (class "Default")
      (node (ref "U4") (pin "9") (pinfunction "R5_9") (pintype "passive+no_connect"))
    )
  )
)
